# DWM1000_rev2.net
KiCad netlist of a schematic drawn in EAGLE
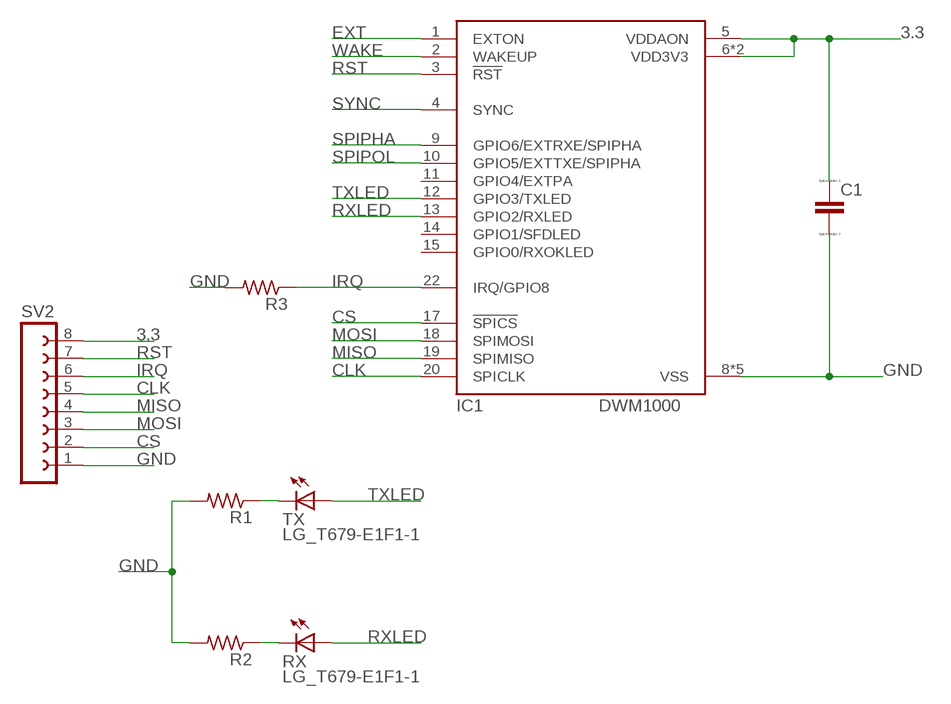
[diagram p0: schematic, sheet 1]

(export (version "E")
  (design (tool "Eeschema 10.0.6"))
  (components
    (comp (ref "C1")
      (value "CC1206")
      (footprint "eagle-import:C1206")
      (libsource (lib "eagle-import") (part "CC1206"))
    )
    (comp (ref "IC1")
      (value "DWM1000")
      (footprint "eagle-import:DWM1000")
      (libsource (lib "eagle-import") (part "DWM1000"))
    )
    (comp (ref "R1")
      (value "R-US_M0805")
      (footprint "eagle-import:M0805")
      (libsource (lib "eagle-import") (part "R-US_M0805"))
    )
    (comp (ref "R2")
      (value "R-US_M0805")
      (footprint "eagle-import:M0805")
      (libsource (lib "eagle-import") (part "R-US_M0805"))
    )
    (comp (ref "R3")
      (value "R-US_M0805")
      (footprint "eagle-import:M0805")
      (libsource (lib "eagle-import") (part "R-US_M0805"))
    )
    (comp (ref "RX")
      (value "LG_T679-E1F1-1")
      (footprint "eagle-import:PLCC2")
      (libsource (lib "eagle-import") (part "_T679-?-1E1F1LG"))
    )
    (comp (ref "SV2")
      (value "FE08-1")
      (footprint "eagle-import:FE08")
      (libsource (lib "eagle-import") (part "FE08-1"))
    )
    (comp (ref "TX")
      (value "LG_T679-E1F1-1")
      (footprint "eagle-import:PLCC2")
      (libsource (lib "eagle-import") (part "_T679-?-1E1F1LG"))
    )
  )
  (nets
    (net (code "1") (name "/3.3") (class "Default")
      (node (ref "C1") (pin "1") (pinfunction "1_1") (pintype "passive"))
      (node (ref "IC1") (pin "5") (pinfunction "VDDAON_5") (pintype "bidirectional"))
      (node (ref "IC1") (pin "6") (pinfunction "VDD3V3_6") (pintype "bidirectional"))
      (node (ref "IC1") (pin "7") (pinfunction "VDD3V3_7") (pintype "bidirectional"))
      (node (ref "SV2") (pin "8") (pinfunction "8_8") (pintype "passive"))
    )
    (net (code "2") (name "/CLK") (class "Default")
      (node (ref "IC1") (pin "20") (pinfunction "SPICLK_20") (pintype "bidirectional"))
      (node (ref "SV2") (pin "5") (pinfunction "5_5") (pintype "passive"))
    )
    (net (code "3") (name "/CS") (class "Default")
      (node (ref "IC1") (pin "17") (pinfunction "~{SPICS}_17") (pintype "bidirectional"))
      (node (ref "SV2") (pin "2") (pinfunction "2_2") (pintype "passive"))
    )
    (net (code "4") (name "/EXT") (class "Default")
      (node (ref "IC1") (pin "1") (pinfunction "EXTON_1") (pintype "bidirectional"))
    )
    (net (code "5") (name "/GND") (class "Default")
      (node (ref "C1") (pin "2") (pinfunction "2_2") (pintype "passive"))
      (node (ref "IC1") (pin "16") (pinfunction "VSS_16") (pintype "bidirectional"))
      (node (ref "IC1") (pin "21") (pinfunction "VSS_21") (pintype "bidirectional"))
      (node (ref "IC1") (pin "23") (pinfunction "VSS_23") (pintype "bidirectional"))
      (node (ref "IC1") (pin "24") (pinfunction "VSS_24") (pintype "bidirectional"))
      (node (ref "IC1") (pin "8") (pinfunction "VSS_8") (pintype "bidirectional"))
      (node (ref "R1") (pin "2") (pinfunction "2_2") (pintype "passive"))
      (node (ref "R2") (pin "2") (pinfunction "2_2") (pintype "passive"))
      (node (ref "R3") (pin "2") (pinfunction "2_2") (pintype "passive"))
      (node (ref "SV2") (pin "1") (pinfunction "1_1") (pintype "passive"))
    )
    (net (code "6") (name "/IRQ") (class "Default")
      (node (ref "IC1") (pin "22") (pinfunction "IRQ/GPIO8_22") (pintype "bidirectional"))
      (node (ref "R3") (pin "1") (pinfunction "1_1") (pintype "passive"))
      (node (ref "SV2") (pin "6") (pinfunction "6_6") (pintype "passive"))
    )
    (net (code "7") (name "/MISO") (class "Default")
      (node (ref "IC1") (pin "19") (pinfunction "SPIMISO_19") (pintype "bidirectional"))
      (node (ref "SV2") (pin "4") (pinfunction "4_4") (pintype "passive"))
    )
    (net (code "8") (name "/MOSI") (class "Default")
      (node (ref "IC1") (pin "18") (pinfunction "SPIMOSI_18") (pintype "bidirectional"))
      (node (ref "SV2") (pin "3") (pinfunction "3_3") (pintype "passive"))
    )
    (net (code "9") (name "/RST") (class "Default")
      (node (ref "IC1") (pin "3") (pinfunction "~{RST}_3") (pintype "bidirectional"))
      (node (ref "SV2") (pin "7") (pinfunction "7_7") (pintype "passive"))
    )
    (net (code "10") (name "/RXLED") (class "Default")
      (node (ref "IC1") (pin "13") (pinfunction "GPIO2/RXLED_13") (pintype "bidirectional"))
      (node (ref "RX") (pin "A") (pinfunction "A_A") (pintype "passive"))
    )
    (net (code "11") (name "/SPIPHA") (class "Default")
      (node (ref "IC1") (pin "9") (pinfunction "GPIO6/EXTRXE/SPIPHA_9") (pintype "bidirectional"))
    )
    (net (code "12") (name "/SPIPOL") (class "Default")
      (node (ref "IC1") (pin "10") (pinfunction "GPIO5/EXTTXE/SPIPHA_10") (pintype "bidirectional"))
    )
    (net (code "13") (name "/SYNC") (class "Default")
      (node (ref "IC1") (pin "4") (pinfunction "SYNC_4") (pintype "bidirectional"))
    )
    (net (code "14") (name "/TXLED") (class "Default")
      (node (ref "IC1") (pin "12") (pinfunction "GPIO3/TXLED_12") (pintype "bidirectional"))
      (node (ref "TX") (pin "A") (pinfunction "A_A") (pintype "passive"))
    )
    (net (code "15") (name "/WAKE") (class "Default")
      (node (ref "IC1") (pin "2") (pinfunction "WAKEUP_2") (pintype "bidirectional"))
    )
    (net (code "16") (name "Net-(R1-Pad1)") (class "Default")
      (node (ref "R1") (pin "1") (pinfunction "1_1") (pintype "passive"))
      (node (ref "TX") (pin "C") (pinfunction "C_C") (pintype "passive"))
    )
    (net (code "17") (name "Net-(R2-Pad1)") (class "Default")
      (node (ref "R2") (pin "1") (pinfunction "1_1") (pintype "passive"))
      (node (ref "RX") (pin "C") (pinfunction "C_C") (pintype "passive"))
    )
    (net (code "18") (name "unconnected-(IC1-GPIO0{slash}RXOKLED-Pad15)") (class "Default")
      (node (ref "IC1") (pin "15") (pinfunction "GPIO0/RXOKLED_15") (pintype "bidirectional"))
    )
    (net (code "19") (name "unconnected-(IC1-GPIO1{slash}SFDLED-Pad14)") (class "Default")
      (node (ref "IC1") (pin "14") (pinfunction "GPIO1/SFDLED_14") (pintype "bidirectional"))
    )
    (net (code "20") (name "unconnected-(IC1-GPIO4{slash}EXTPA-Pad11)") (class "Default")
      (node (ref "IC1") (pin "11") (pinfunction "GPIO4/EXTPA_11") (pintype "bidirectional"))
    )
  )
)
